# POWER.net
KiCad netlist of a schematic drawn in Altium Designer
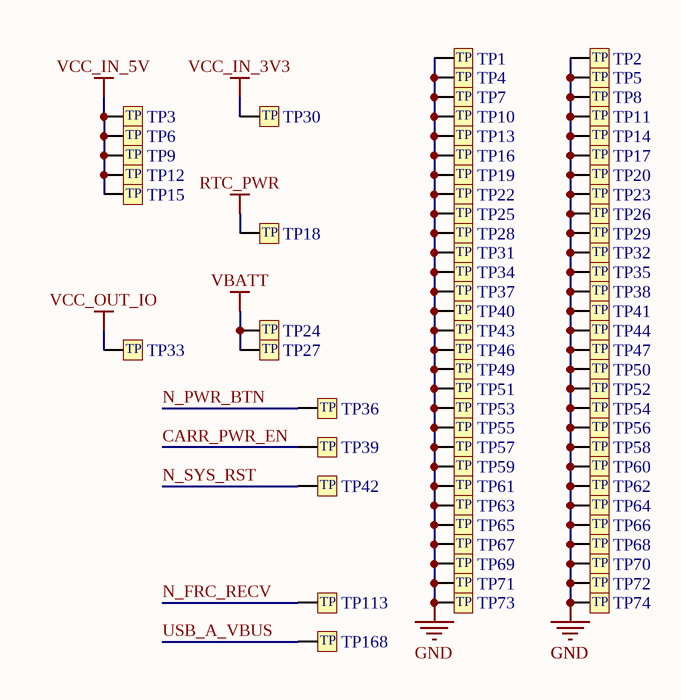
[diagram p0: POWER.SchDoc]

(export (version "E")
  (design (tool "Eeschema 10.0.6"))
  (components
    (comp (ref "TP1")
      (value "TP_0P8MM")
      (footprint "TP_0P8MM")
      (description "OSM Footprint 0P8 LGA Ball")
      (libsource (lib "Jumper") (part "TP_0P8MM"))
    )
    (comp (ref "TP2")
      (value "TP_0P8MM")
      (footprint "TP_0P8MM")
      (description "OSM Footprint 0P8 LGA Ball")
      (libsource (lib "Jumper") (part "TP_0P8MM"))
    )
    (comp (ref "TP3")
      (value "TP_0P8MM")
      (footprint "TP_0P8MM")
      (description "OSM Footprint 0P8 LGA Ball")
      (libsource (lib "Jumper") (part "TP_0P8MM"))
    )
    (comp (ref "TP4")
      (value "TP_0P8MM")
      (footprint "TP_0P8MM")
      (description "OSM Footprint 0P8 LGA Ball")
      (libsource (lib "Jumper") (part "TP_0P8MM"))
    )
    (comp (ref "TP5")
      (value "TP_0P8MM")
      (footprint "TP_0P8MM")
      (description "OSM Footprint 0P8 LGA Ball")
      (libsource (lib "Jumper") (part "TP_0P8MM"))
    )
    (comp (ref "TP6")
      (value "TP_0P8MM")
      (footprint "TP_0P8MM")
      (description "OSM Footprint 0P8 LGA Ball")
      (libsource (lib "Jumper") (part "TP_0P8MM"))
    )
    (comp (ref "TP7")
      (value "TP_0P8MM")
      (footprint "TP_0P8MM")
      (description "OSM Footprint 0P8 LGA Ball")
      (libsource (lib "Jumper") (part "TP_0P8MM"))
    )
    (comp (ref "TP8")
      (value "TP_0P8MM")
      (footprint "TP_0P8MM")
      (description "OSM Footprint 0P8 LGA Ball")
      (libsource (lib "Jumper") (part "TP_0P8MM"))
    )
    (comp (ref "TP9")
      (value "TP_0P8MM")
      (footprint "TP_0P8MM")
      (description "OSM Footprint 0P8 LGA Ball")
      (libsource (lib "Jumper") (part "TP_0P8MM"))
    )
    (comp (ref "TP10")
      (value "TP_0P8MM")
      (footprint "TP_0P8MM")
      (description "OSM Footprint 0P8 LGA Ball")
      (libsource (lib "Jumper") (part "TP_0P8MM"))
    )
    (comp (ref "TP11")
      (value "TP_0P8MM")
      (footprint "TP_0P8MM")
      (description "OSM Footprint 0P8 LGA Ball")
      (libsource (lib "Jumper") (part "TP_0P8MM"))
    )
    (comp (ref "TP12")
      (value "TP_0P8MM")
      (footprint "TP_0P8MM")
      (description "OSM Footprint 0P8 LGA Ball")
      (libsource (lib "Jumper") (part "TP_0P8MM"))
    )
    (comp (ref "TP13")
      (value "TP_0P8MM")
      (footprint "TP_0P8MM")
      (description "OSM Footprint 0P8 LGA Ball")
      (libsource (lib "Jumper") (part "TP_0P8MM"))
    )
    (comp (ref "TP14")
      (value "TP_0P8MM")
      (footprint "TP_0P8MM")
      (description "OSM Footprint 0P8 LGA Ball")
      (libsource (lib "Jumper") (part "TP_0P8MM"))
    )
    (comp (ref "TP15")
      (value "TP_0P8MM")
      (footprint "TP_0P8MM")
      (description "OSM Footprint 0P8 LGA Ball")
      (libsource (lib "Jumper") (part "TP_0P8MM"))
    )
    (comp (ref "TP16")
      (value "TP_0P8MM")
      (footprint "TP_0P8MM")
      (description "OSM Footprint 0P8 LGA Ball")
      (libsource (lib "Jumper") (part "TP_0P8MM"))
    )
    (comp (ref "TP17")
      (value "TP_0P8MM")
      (footprint "TP_0P8MM")
      (description "OSM Footprint 0P8 LGA Ball")
      (libsource (lib "Jumper") (part "TP_0P8MM"))
    )
    (comp (ref "TP18")
      (value "TP_0P8MM")
      (footprint "TP_0P8MM")
      (description "OSM Footprint 0P8 LGA Ball")
      (libsource (lib "Jumper") (part "TP_0P8MM"))
    )
    (comp (ref "TP19")
      (value "TP_0P8MM")
      (footprint "TP_0P8MM")
      (description "OSM Footprint 0P8 LGA Ball")
      (libsource (lib "Jumper") (part "TP_0P8MM"))
    )
    (comp (ref "TP20")
      (value "TP_0P8MM")
      (footprint "TP_0P8MM")
      (description "OSM Footprint 0P8 LGA Ball")
      (libsource (lib "Jumper") (part "TP_0P8MM"))
    )
    (comp (ref "TP22")
      (value "TP_0P8MM")
      (footprint "TP_0P8MM")
      (description "OSM Footprint 0P8 LGA Ball")
      (libsource (lib "Jumper") (part "TP_0P8MM"))
    )
    (comp (ref "TP23")
      (value "TP_0P8MM")
      (footprint "TP_0P8MM")
      (description "OSM Footprint 0P8 LGA Ball")
      (libsource (lib "Jumper") (part "TP_0P8MM"))
    )
    (comp (ref "TP24")
      (value "TP_0P8MM")
      (footprint "TP_0P8MM")
      (description "OSM Footprint 0P8 LGA Ball")
      (libsource (lib "Jumper") (part "TP_0P8MM"))
    )
    (comp (ref "TP25")
      (value "TP_0P8MM")
      (footprint "TP_0P8MM")
      (description "OSM Footprint 0P8 LGA Ball")
      (libsource (lib "Jumper") (part "TP_0P8MM"))
    )
    (comp (ref "TP26")
      (value "TP_0P8MM")
      (footprint "TP_0P8MM")
      (description "OSM Footprint 0P8 LGA Ball")
      (libsource (lib "Jumper") (part "TP_0P8MM"))
    )
    (comp (ref "TP27")
      (value "TP_0P8MM")
      (footprint "TP_0P8MM")
      (description "OSM Footprint 0P8 LGA Ball")
      (libsource (lib "Jumper") (part "TP_0P8MM"))
    )
    (comp (ref "TP28")
      (value "TP_0P8MM")
      (footprint "TP_0P8MM")
      (description "OSM Footprint 0P8 LGA Ball")
      (libsource (lib "Jumper") (part "TP_0P8MM"))
    )
    (comp (ref "TP29")
      (value "TP_0P8MM")
      (footprint "TP_0P8MM")
      (description "OSM Footprint 0P8 LGA Ball")
      (libsource (lib "Jumper") (part "TP_0P8MM"))
    )
    (comp (ref "TP30")
      (value "TP_0P8MM")
      (footprint "TP_0P8MM")
      (description "OSM Footprint 0P8 LGA Ball")
      (libsource (lib "Jumper") (part "TP_0P8MM"))
    )
    (comp (ref "TP31")
      (value "TP_0P8MM")
      (footprint "TP_0P8MM")
      (description "OSM Footprint 0P8 LGA Ball")
      (libsource (lib "Jumper") (part "TP_0P8MM"))
    )
    (comp (ref "TP32")
      (value "TP_0P8MM")
      (footprint "TP_0P8MM")
      (description "OSM Footprint 0P8 LGA Ball")
      (libsource (lib "Jumper") (part "TP_0P8MM"))
    )
    (comp (ref "TP33")
      (value "TP_0P8MM")
      (footprint "TP_0P8MM")
      (description "OSM Footprint 0P8 LGA Ball")
      (libsource (lib "Jumper") (part "TP_0P8MM"))
    )
    (comp (ref "TP34")
      (value "TP_0P8MM")
      (footprint "TP_0P8MM")
      (description "OSM Footprint 0P8 LGA Ball")
      (libsource (lib "Jumper") (part "TP_0P8MM"))
    )
    (comp (ref "TP35")
      (value "TP_0P8MM")
      (footprint "TP_0P8MM")
      (description "OSM Footprint 0P8 LGA Ball")
      (libsource (lib "Jumper") (part "TP_0P8MM"))
    )
    (comp (ref "TP36")
      (value "TP_0P8MM")
      (footprint "TP_0P8MM")
      (description "OSM Footprint 0P8 LGA Ball")
      (libsource (lib "Jumper") (part "TP_0P8MM"))
    )
    (comp (ref "TP37")
      (value "TP_0P8MM")
      (footprint "TP_0P8MM")
      (description "OSM Footprint 0P8 LGA Ball")
      (libsource (lib "Jumper") (part "TP_0P8MM"))
    )
    (comp (ref "TP38")
      (value "TP_0P8MM")
      (footprint "TP_0P8MM")
      (description "OSM Footprint 0P8 LGA Ball")
      (libsource (lib "Jumper") (part "TP_0P8MM"))
    )
    (comp (ref "TP39")
      (value "TP_0P8MM")
      (footprint "TP_0P8MM")
      (description "OSM Footprint 0P8 LGA Ball")
      (libsource (lib "Jumper") (part "TP_0P8MM"))
    )
    (comp (ref "TP40")
      (value "TP_0P8MM")
      (footprint "TP_0P8MM")
      (description "OSM Footprint 0P8 LGA Ball")
      (libsource (lib "Jumper") (part "TP_0P8MM"))
    )
    (comp (ref "TP41")
      (value "TP_0P8MM")
      (footprint "TP_0P8MM")
      (description "OSM Footprint 0P8 LGA Ball")
      (libsource (lib "Jumper") (part "TP_0P8MM"))
    )
    (comp (ref "TP42")
      (value "TP_0P8MM")
      (footprint "TP_0P8MM")
      (description "OSM Footprint 0P8 LGA Ball")
      (libsource (lib "Jumper") (part "TP_0P8MM"))
    )
    (comp (ref "TP43")
      (value "TP_0P8MM")
      (footprint "TP_0P8MM")
      (description "OSM Footprint 0P8 LGA Ball")
      (libsource (lib "Jumper") (part "TP_0P8MM"))
    )
    (comp (ref "TP44")
      (value "TP_0P8MM")
      (footprint "TP_0P8MM")
      (description "OSM Footprint 0P8 LGA Ball")
      (libsource (lib "Jumper") (part "TP_0P8MM"))
    )
    (comp (ref "TP46")
      (value "TP_0P8MM")
      (footprint "TP_0P8MM")
      (description "OSM Footprint 0P8 LGA Ball")
      (libsource (lib "Jumper") (part "TP_0P8MM"))
    )
    (comp (ref "TP47")
      (value "TP_0P8MM")
      (footprint "TP_0P8MM")
      (description "OSM Footprint 0P8 LGA Ball")
      (libsource (lib "Jumper") (part "TP_0P8MM"))
    )
    (comp (ref "TP49")
      (value "TP_0P8MM")
      (footprint "TP_0P8MM")
      (description "OSM Footprint 0P8 LGA Ball")
      (libsource (lib "Jumper") (part "TP_0P8MM"))
    )
    (comp (ref "TP50")
      (value "TP_0P8MM")
      (footprint "TP_0P8MM")
      (description "OSM Footprint 0P8 LGA Ball")
      (libsource (lib "Jumper") (part "TP_0P8MM"))
    )
    (comp (ref "TP51")
      (value "TP_0P8MM")
      (footprint "TP_0P8MM")
      (description "OSM Footprint 0P8 LGA Ball")
      (libsource (lib "Jumper") (part "TP_0P8MM"))
    )
    (comp (ref "TP52")
      (value "TP_0P8MM")
      (footprint "TP_0P8MM")
      (description "OSM Footprint 0P8 LGA Ball")
      (libsource (lib "Jumper") (part "TP_0P8MM"))
    )
    (comp (ref "TP53")
      (value "TP_0P8MM")
      (footprint "TP_0P8MM")
      (description "OSM Footprint 0P8 LGA Ball")
      (libsource (lib "Jumper") (part "TP_0P8MM"))
    )
    (comp (ref "TP54")
      (value "TP_0P8MM")
      (footprint "TP_0P8MM")
      (description "OSM Footprint 0P8 LGA Ball")
      (libsource (lib "Jumper") (part "TP_0P8MM"))
    )
    (comp (ref "TP55")
      (value "TP_0P8MM")
      (footprint "TP_0P8MM")
      (description "OSM Footprint 0P8 LGA Ball")
      (libsource (lib "Jumper") (part "TP_0P8MM"))
    )
    (comp (ref "TP56")
      (value "TP_0P8MM")
      (footprint "TP_0P8MM")
      (description "OSM Footprint 0P8 LGA Ball")
      (libsource (lib "Jumper") (part "TP_0P8MM"))
    )
    (comp (ref "TP57")
      (value "TP_0P8MM")
      (footprint "TP_0P8MM")
      (description "OSM Footprint 0P8 LGA Ball")
      (libsource (lib "Jumper") (part "TP_0P8MM"))
    )
    (comp (ref "TP58")
      (value "TP_0P8MM")
      (footprint "TP_0P8MM")
      (description "OSM Footprint 0P8 LGA Ball")
      (libsource (lib "Jumper") (part "TP_0P8MM"))
    )
    (comp (ref "TP59")
      (value "TP_0P8MM")
      (footprint "TP_0P8MM")
      (description "OSM Footprint 0P8 LGA Ball")
      (libsource (lib "Jumper") (part "TP_0P8MM"))
    )
    (comp (ref "TP60")
      (value "TP_0P8MM")
      (footprint "TP_0P8MM")
      (description "OSM Footprint 0P8 LGA Ball")
      (libsource (lib "Jumper") (part "TP_0P8MM"))
    )
    (comp (ref "TP61")
      (value "TP_0P8MM")
      (footprint "TP_0P8MM")
      (description "OSM Footprint 0P8 LGA Ball")
      (libsource (lib "Jumper") (part "TP_0P8MM"))
    )
    (comp (ref "TP62")
      (value "TP_0P8MM")
      (footprint "TP_0P8MM")
      (description "OSM Footprint 0P8 LGA Ball")
      (libsource (lib "Jumper") (part "TP_0P8MM"))
    )
    (comp (ref "TP63")
      (value "TP_0P8MM")
      (footprint "TP_0P8MM")
      (description "OSM Footprint 0P8 LGA Ball")
      (libsource (lib "Jumper") (part "TP_0P8MM"))
    )
    (comp (ref "TP64")
      (value "TP_0P8MM")
      (footprint "TP_0P8MM")
      (description "OSM Footprint 0P8 LGA Ball")
      (libsource (lib "Jumper") (part "TP_0P8MM"))
    )
    (comp (ref "TP65")
      (value "TP_0P8MM")
      (footprint "TP_0P8MM")
      (description "OSM Footprint 0P8 LGA Ball")
      (libsource (lib "Jumper") (part "TP_0P8MM"))
    )
    (comp (ref "TP66")
      (value "TP_0P8MM")
      (footprint "TP_0P8MM")
      (description "OSM Footprint 0P8 LGA Ball")
      (libsource (lib "Jumper") (part "TP_0P8MM"))
    )
    (comp (ref "TP67")
      (value "TP_0P8MM")
      (footprint "TP_0P8MM")
      (description "OSM Footprint 0P8 LGA Ball")
      (libsource (lib "Jumper") (part "TP_0P8MM"))
    )
    (comp (ref "TP68")
      (value "TP_0P8MM")
      (footprint "TP_0P8MM")
      (description "OSM Footprint 0P8 LGA Ball")
      (libsource (lib "Jumper") (part "TP_0P8MM"))
    )
    (comp (ref "TP69")
      (value "TP_0P8MM")
      (footprint "TP_0P8MM")
      (description "OSM Footprint 0P8 LGA Ball")
      (libsource (lib "Jumper") (part "TP_0P8MM"))
    )
    (comp (ref "TP70")
      (value "TP_0P8MM")
      (footprint "TP_0P8MM")
      (description "OSM Footprint 0P8 LGA Ball")
      (libsource (lib "Jumper") (part "TP_0P8MM"))
    )
    (comp (ref "TP71")
      (value "TP_0P8MM")
      (footprint "TP_0P8MM")
      (description "OSM Footprint 0P8 LGA Ball")
      (libsource (lib "Jumper") (part "TP_0P8MM"))
    )
    (comp (ref "TP72")
      (value "TP_0P8MM")
      (footprint "TP_0P8MM")
      (description "OSM Footprint 0P8 LGA Ball")
      (libsource (lib "Jumper") (part "TP_0P8MM"))
    )
    (comp (ref "TP73")
      (value "TP_0P8MM")
      (footprint "TP_0P8MM")
      (description "OSM Footprint 0P8 LGA Ball")
      (libsource (lib "Jumper") (part "TP_0P8MM"))
    )
    (comp (ref "TP74")
      (value "TP_0P8MM")
      (footprint "TP_0P8MM")
      (description "OSM Footprint 0P8 LGA Ball")
      (libsource (lib "Jumper") (part "TP_0P8MM"))
    )
    (comp (ref "TP113")
      (value "TP_0P8MM")
      (footprint "TP_0P8MM")
      (description "OSM Footprint 0P8 LGA Ball")
      (libsource (lib "Jumper") (part "TP_0P8MM"))
    )
    (comp (ref "TP168")
      (value "TP_0P8MM")
      (footprint "TP_0P8MM")
      (description "OSM Footprint 0P8 LGA Ball")
      (libsource (lib "Jumper") (part "TP_0P8MM"))
    )
  )
  (nets
    (net (code "1") (name "/CARR_PWR_EN") (class "Default")
      (node (ref "TP39") (pin "1") (pinfunction "1_1") (pintype "passive"))
    )
    (net (code "2") (name "/N_FRC_RECV") (class "Default")
      (node (ref "TP113") (pin "1") (pinfunction "1_1") (pintype "passive"))
    )
    (net (code "3") (name "/N_PWR_BTN") (class "Default")
      (node (ref "TP36") (pin "1") (pinfunction "1_1") (pintype "passive"))
    )
    (net (code "4") (name "/N_SYS_RST") (class "Default")
      (node (ref "TP42") (pin "1") (pinfunction "1_1") (pintype "passive"))
    )
    (net (code "5") (name "/USB_A_VBUS") (class "Default")
      (node (ref "TP168") (pin "1") (pinfunction "1_1") (pintype "passive"))
    )
    (net (code "6") (name "GND") (class "Default")
      (node (ref "TP1") (pin "1") (pinfunction "1_1") (pintype "passive"))
      (node (ref "TP10") (pin "1") (pinfunction "1_1") (pintype "passive"))
      (node (ref "TP11") (pin "1") (pinfunction "1_1") (pintype "passive"))
      (node (ref "TP13") (pin "1") (pinfunction "1_1") (pintype "passive"))
      (node (ref "TP14") (pin "1") (pinfunction "1_1") (pintype "passive"))
      (node (ref "TP16") (pin "1") (pinfunction "1_1") (pintype "passive"))
      (node (ref "TP17") (pin "1") (pinfunction "1_1") (pintype "passive"))
      (node (ref "TP19") (pin "1") (pinfunction "1_1") (pintype "passive"))
      (node (ref "TP2") (pin "1") (pinfunction "1_1") (pintype "passive"))
      (node (ref "TP20") (pin "1") (pinfunction "1_1") (pintype "passive"))
      (node (ref "TP22") (pin "1") (pinfunction "1_1") (pintype "passive"))
      (node (ref "TP23") (pin "1") (pinfunction "1_1") (pintype "passive"))
      (node (ref "TP25") (pin "1") (pinfunction "1_1") (pintype "passive"))
      (node (ref "TP26") (pin "1") (pinfunction "1_1") (pintype "passive"))
      (node (ref "TP28") (pin "1") (pinfunction "1_1") (pintype "passive"))
      (node (ref "TP29") (pin "1") (pinfunction "1_1") (pintype "passive"))
      (node (ref "TP31") (pin "1") (pinfunction "1_1") (pintype "passive"))
      (node (ref "TP32") (pin "1") (pinfunction "1_1") (pintype "passive"))
      (node (ref "TP34") (pin "1") (pinfunction "1_1") (pintype "passive"))
      (node (ref "TP35") (pin "1") (pinfunction "1_1") (pintype "passive"))
      (node (ref "TP37") (pin "1") (pinfunction "1_1") (pintype "passive"))
      (node (ref "TP38") (pin "1") (pinfunction "1_1") (pintype "passive"))
      (node (ref "TP4") (pin "1") (pinfunction "1_1") (pintype "passive"))
      (node (ref "TP40") (pin "1") (pinfunction "1_1") (pintype "passive"))
      (node (ref "TP41") (pin "1") (pinfunction "1_1") (pintype "passive"))
      (node (ref "TP43") (pin "1") (pinfunction "1_1") (pintype "passive"))
      (node (ref "TP44") (pin "1") (pinfunction "1_1") (pintype "passive"))
      (node (ref "TP46") (pin "1") (pinfunction "1_1") (pintype "passive"))
      (node (ref "TP47") (pin "1") (pinfunction "1_1") (pintype "passive"))
      (node (ref "TP49") (pin "1") (pinfunction "1_1") (pintype "passive"))
      (node (ref "TP5") (pin "1") (pinfunction "1_1") (pintype "passive"))
      (node (ref "TP50") (pin "1") (pinfunction "1_1") (pintype "passive"))
      (node (ref "TP51") (pin "1") (pinfunction "1_1") (pintype "passive"))
      (node (ref "TP52") (pin "1") (pinfunction "1_1") (pintype "passive"))
      (node (ref "TP53") (pin "1") (pinfunction "1_1") (pintype "passive"))
      (node (ref "TP54") (pin "1") (pinfunction "1_1") (pintype "passive"))
      (node (ref "TP55") (pin "1") (pinfunction "1_1") (pintype "passive"))
      (node (ref "TP56") (pin "1") (pinfunction "1_1") (pintype "passive"))
      (node (ref "TP57") (pin "1") (pinfunction "1_1") (pintype "passive"))
      (node (ref "TP58") (pin "1") (pinfunction "1_1") (pintype "passive"))
      (node (ref "TP59") (pin "1") (pinfunction "1_1") (pintype "passive"))
      (node (ref "TP60") (pin "1") (pinfunction "1_1") (pintype "passive"))
      (node (ref "TP61") (pin "1") (pinfunction "1_1") (pintype "passive"))
      (node (ref "TP62") (pin "1") (pinfunction "1_1") (pintype "passive"))
      (node (ref "TP63") (pin "1") (pinfunction "1_1") (pintype "passive"))
      (node (ref "TP64") (pin "1") (pinfunction "1_1") (pintype "passive"))
      (node (ref "TP65") (pin "1") (pinfunction "1_1") (pintype "passive"))
      (node (ref "TP66") (pin "1") (pinfunction "1_1") (pintype "passive"))
      (node (ref "TP67") (pin "1") (pinfunction "1_1") (pintype "passive"))
      (node (ref "TP68") (pin "1") (pinfunction "1_1") (pintype "passive"))
      (node (ref "TP69") (pin "1") (pinfunction "1_1") (pintype "passive"))
      (node (ref "TP7") (pin "1") (pinfunction "1_1") (pintype "passive"))
      (node (ref "TP70") (pin "1") (pinfunction "1_1") (pintype "passive"))
      (node (ref "TP71") (pin "1") (pinfunction "1_1") (pintype "passive"))
      (node (ref "TP72") (pin "1") (pinfunction "1_1") (pintype "passive"))
      (node (ref "TP73") (pin "1") (pinfunction "1_1") (pintype "passive"))
      (node (ref "TP74") (pin "1") (pinfunction "1_1") (pintype "passive"))
      (node (ref "TP8") (pin "1") (pinfunction "1_1") (pintype "passive"))
    )
    (net (code "7") (name "RTC_PWR") (class "Default")
      (node (ref "TP18") (pin "1") (pinfunction "1_1") (pintype "passive"))
    )
    (net (code "8") (name "VBATT") (class "Default")
      (node (ref "TP24") (pin "1") (pinfunction "1_1") (pintype "passive"))
      (node (ref "TP27") (pin "1") (pinfunction "1_1") (pintype "passive"))
    )
    (net (code "9") (name "VCC_IN_3V3") (class "Default")
      (node (ref "TP30") (pin "1") (pinfunction "1_1") (pintype "passive"))
    )
    (net (code "10") (name "VCC_IN_5V") (class "Default")
      (node (ref "TP12") (pin "1") (pinfunction "1_1") (pintype "passive"))
      (node (ref "TP15") (pin "1") (pinfunction "1_1") (pintype "passive"))
      (node (ref "TP3") (pin "1") (pinfunction "1_1") (pintype "passive"))
      (node (ref "TP6") (pin "1") (pinfunction "1_1") (pintype "passive"))
      (node (ref "TP9") (pin "1") (pinfunction "1_1") (pintype "passive"))
    )
    (net (code "11") (name "VCC_OUT_IO") (class "Default")
      (node (ref "TP33") (pin "1") (pinfunction "1_1") (pintype "passive"))
    )
  )
)
